# RA3003-A-1.net
KiCad netlist of a schematic drawn in Altium Designer
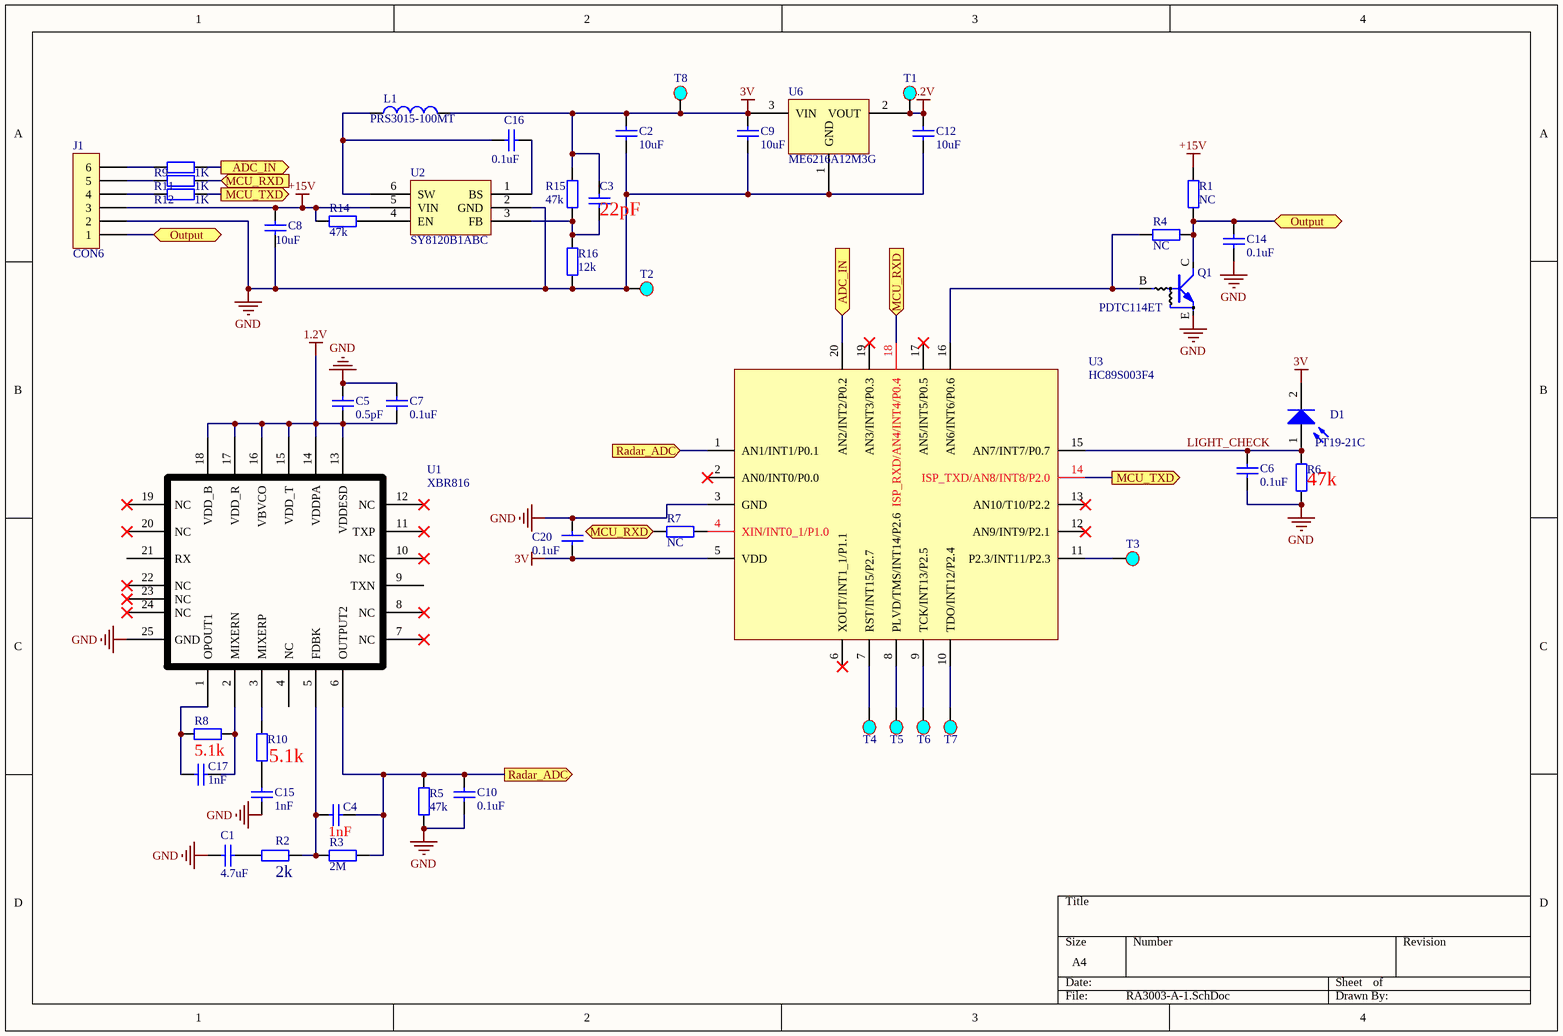
[diagram p0: RA3003-A-1.SchDoc]

(export (version "E")
  (design (tool "Eeschema 10.0.6"))
  (components
    (comp (ref "C1")
      (value "4.7uF")
      (footprint "C0402")
      (description "Capacitor")
      (fields (field (name "PUBLISHER") "Altium Limited"))
      (libsource (lib "Miscellaneous Devices") (part "Cap"))
    )
    (comp (ref "C2")
      (value "10uF")
      (footprint "C0402")
      (description "Capacitor")
      (fields (field (name "PUBLISHER") "Altium Limited"))
      (libsource (lib "Miscellaneous Devices") (part "Cap"))
    )
    (comp (ref "C3")
      (value "22pF")
      (footprint "C0402")
      (description "Capacitor")
      (fields (field (name "PUBLISHER") "Altium Limited"))
      (libsource (lib "Miscellaneous Devices") (part "Cap"))
    )
    (comp (ref "C4")
      (value "1nF")
      (footprint "C0402")
      (description "Capacitor")
      (fields (field (name "PUBLISHER") "Altium Limited"))
      (libsource (lib "Miscellaneous Devices") (part "Cap"))
    )
    (comp (ref "C5")
      (value "0.5pF")
      (footprint "C0402")
      (description "Capacitor")
      (fields (field (name "PUBLISHER") "Altium Limited"))
      (libsource (lib "Miscellaneous Devices") (part "Cap"))
    )
    (comp (ref "C6")
      (value "0.1uF")
      (footprint "C0402")
      (description "Capacitor")
      (fields (field (name "PUBLISHER") "Altium Limited"))
      (libsource (lib "Miscellaneous Devices") (part "Cap"))
    )
    (comp (ref "C7")
      (value "0.1uF")
      (footprint "C0402")
      (description "Capacitor")
      (fields (field (name "PUBLISHER") "Altium Limited"))
      (libsource (lib "Miscellaneous Devices") (part "Cap"))
    )
    (comp (ref "C8")
      (value "10uF")
      (footprint "C0603")
      (description "Capacitor")
      (fields (field (name "PUBLISHER") "Altium Limited"))
      (libsource (lib "Miscellaneous Devices") (part "Cap"))
    )
    (comp (ref "C9")
      (value "10uF")
      (footprint "C0402")
      (description "Capacitor")
      (fields (field (name "PUBLISHER") "Altium Limited"))
      (libsource (lib "Miscellaneous Devices") (part "Cap"))
    )
    (comp (ref "C10")
      (value "0.1uF")
      (footprint "C0402")
      (description "Capacitor")
      (fields (field (name "PUBLISHER") "Altium Limited"))
      (libsource (lib "Miscellaneous Devices") (part "Cap"))
    )
    (comp (ref "C12")
      (value "10uF")
      (footprint "C0402")
      (description "Capacitor")
      (fields (field (name "PUBLISHER") "Altium Limited"))
      (libsource (lib "Miscellaneous Devices") (part "Cap"))
    )
    (comp (ref "C14")
      (value "0.1uF")
      (footprint "C0402")
      (description "Capacitor")
      (fields (field (name "PUBLISHER") "Altium Limited"))
      (libsource (lib "Miscellaneous Devices") (part "Cap"))
    )
    (comp (ref "C15")
      (value "1nF")
      (footprint "C0402")
      (description "Capacitor")
      (fields (field (name "PUBLISHER") "Altium Limited"))
      (libsource (lib "Miscellaneous Devices") (part "Cap"))
    )
    (comp (ref "C16")
      (value "0.1uF")
      (footprint "C0402")
      (description "Capacitor")
      (fields (field (name "PUBLISHER") "Altium Limited"))
      (libsource (lib "Miscellaneous Devices") (part "Cap"))
    )
    (comp (ref "C17")
      (value "1nF")
      (footprint "C0402")
      (description "Capacitor")
      (fields (field (name "PUBLISHER") "Altium Limited"))
      (libsource (lib "Miscellaneous Devices") (part "Cap"))
    )
    (comp (ref "C20")
      (value "0.1uF")
      (footprint "C0402")
      (description "Capacitor")
      (fields (field (name "PUBLISHER") "Altium Limited"))
      (libsource (lib "Miscellaneous Devices") (part "Cap"))
    )
    (comp (ref "D1")
      (value "PT19-21C")
      (footprint "LED-0603")
      (description "Photosensitive Diode")
      (fields (field (name "PUBLISHER") "Altium Limited"))
      (libsource (lib "Miscellaneous Devices") (part "Photo Sen"))
    )
    (comp (ref "J1")
      (value "CON6")
      (footprint "CON 6PIN-1-2.0-DIP-P")
      (description "Connector")
      (libsource (lib "标准原理图库（特种板）") (part "CON6"))
    )
    (comp (ref "L1")
      (value "PRS3015-100MT")
      (footprint "PRS3015")
      (description "Inductor")
      (fields (field (name "PUBLISHER") "Altium Limited"))
      (libsource (lib "Miscellaneous Devices") (part "Inductor"))
    )
    (comp (ref "Q1")
      (value "PDTC114ET")
      (footprint "SOT-23(BEC)")
      (description "三极管")
      (libsource (lib "标准原理图库（特种板）") (part "PDTC114ET"))
    )
    (comp (ref "R1")
      (value "NC")
      (footprint "R0402")
      (description "Resistor")
      (fields (field (name "PUBLISHER") "Altium Limited"))
      (libsource (lib "Miscellaneous Devices") (part "Res2"))
    )
    (comp (ref "R2")
      (value "2k")
      (footprint "R0402")
      (description "Resistor")
      (fields (field (name "PUBLISHER") "Altium Limited"))
      (libsource (lib "") (part "Res2_3"))
    )
    (comp (ref "R3")
      (value "2M")
      (footprint "R0402")
      (description "Resistor")
      (fields (field (name "PUBLISHER") "Altium Limited"))
      (libsource (lib "") (part "Res2_1"))
    )
    (comp (ref "R4")
      (value "NC")
      (footprint "R0402")
      (description "Resistor")
      (fields (field (name "PUBLISHER") "Altium Limited"))
      (libsource (lib "") (part "Res2_3"))
    )
    (comp (ref "R5")
      (value "47k")
      (footprint "R0402")
      (description "Resistor")
      (fields (field (name "PUBLISHER") "Altium Limited"))
      (libsource (lib "Miscellaneous Devices") (part "Res2"))
    )
    (comp (ref "R6")
      (value "47k")
      (footprint "R0402")
      (description "Resistor")
      (fields (field (name "PUBLISHER") "Altium Limited"))
      (libsource (lib "Miscellaneous Devices") (part "Res2"))
    )
    (comp (ref "R7")
      (value "NC")
      (footprint "R0402")
      (description "Resistor")
      (fields (field (name "PUBLISHER") "Altium Limited"))
      (libsource (lib "") (part "Res2_3"))
    )
    (comp (ref "R8")
      (value "5.1k")
      (footprint "R0402")
      (description "Resistor")
      (fields (field (name "PUBLISHER") "Altium Limited"))
      (libsource (lib "") (part "Res2_1"))
    )
    (comp (ref "R9")
      (value "1K")
      (footprint "R0402")
      (description "Resistor")
      (fields (field (name "PUBLISHER") "Altium Limited"))
      (libsource (lib "") (part "Res2_1"))
    )
    (comp (ref "R10")
      (value "5.1k")
      (footprint "R0402")
      (description "Resistor")
      (fields (field (name "PUBLISHER") "Altium Limited"))
      (libsource (lib "Miscellaneous Devices") (part "Res2"))
    )
    (comp (ref "R11")
      (value "1K")
      (footprint "R0402")
      (description "Resistor")
      (fields (field (name "PUBLISHER") "Altium Limited"))
      (libsource (lib "") (part "Res2_1"))
    )
    (comp (ref "R12")
      (value "1K")
      (footprint "R0402")
      (description "Resistor")
      (fields (field (name "PUBLISHER") "Altium Limited"))
      (libsource (lib "") (part "Res2_1"))
    )
    (comp (ref "R14")
      (value "47k")
      (footprint "R0402")
      (description "Resistor")
      (fields (field (name "PUBLISHER") "Altium Limited"))
      (libsource (lib "") (part "Res2_1"))
    )
    (comp (ref "R15")
      (value "47k")
      (footprint "R0402")
      (description "Resistor")
      (fields (field (name "PUBLISHER") "Altium Limited"))
      (libsource (lib "") (part "Res2_2"))
    )
    (comp (ref "R16")
      (value "12k")
      (footprint "R0402")
      (description "Resistor")
      (fields (field (name "PUBLISHER") "Altium Limited"))
      (libsource (lib "") (part "Res2_2"))
    )
    (comp (ref "T1")
      (value "~")
      (footprint "TestPoints")
      (description "TestPoints")
      (libsource (lib "标准原理图库（特种板）") (part "TestPoints"))
    )
    (comp (ref "T2")
      (value "~")
      (footprint "TestPoints")
      (description "TestPoints")
      (libsource (lib "标准原理图库（特种板）") (part "TestPoints"))
    )
    (comp (ref "T3")
      (value "~")
      (footprint "TestPoints")
      (description "TestPoints")
      (libsource (lib "标准原理图库（特种板）") (part "TestPoints"))
    )
    (comp (ref "T4")
      (value "~")
      (footprint "TestPoints")
      (description "TestPoints")
      (libsource (lib "标准原理图库（特种板）") (part "TestPoints"))
    )
    (comp (ref "T5")
      (value "~")
      (footprint "TestPoints")
      (description "TestPoints")
      (libsource (lib "标准原理图库（特种板）") (part "TestPoints"))
    )
    (comp (ref "T6")
      (value "~")
      (footprint "TestPoints")
      (description "TestPoints")
      (libsource (lib "标准原理图库（特种板）") (part "TestPoints"))
    )
    (comp (ref "T7")
      (value "~")
      (footprint "TestPoints")
      (description "TestPoints")
      (libsource (lib "标准原理图库（特种板）") (part "TestPoints"))
    )
    (comp (ref "T8")
      (value "~")
      (footprint "TestPoints")
      (description "TestPoints")
      (libsource (lib "标准原理图库（特种板）") (part "TestPoints"))
    )
    (comp (ref "U1") (value "XBR816") (footprint "XBR816") (libsource (lib "Schlib1") (part "XBR1000_24_1")))
    (comp (ref "U2") (value "SY8120B1ABC") (footprint "SOT-23-6") (libsource (lib "Schlib1") (part "H9108")))
    (comp (ref "U3")
      (value "HC89S003F4")
      (footprint "QFN20(3*3)")
      (description "MCU")
      (libsource (lib "标准原理图库（特种板）") (part "HC89S003F4"))
    )
    (comp (ref "U6")
      (value "ME6216A12M3G")
      (footprint "SOT-23-L")
      (libsource (lib "Schlib1") (part "SSP6206"))
    )
  )
  (nets
    (net (code "1") (name "+15V") (class "Default")
      (node (ref "C8") (pin "1") (pinfunction "1_1") (pintype "passive"))
      (node (ref "J1") (pin "3") (pinfunction "3_3") (pintype "passive"))
      (node (ref "R1") (pin "1") (pinfunction "1_1") (pintype "passive"))
      (node (ref "R14") (pin "2") (pinfunction "2_2") (pintype "passive"))
      (node (ref "U2") (pin "5") (pinfunction "VIN_5") (pintype "passive"))
    )
    (net (code "2") (name "/ADC_IN") (class "Default")
      (node (ref "R9") (pin "1") (pinfunction "1_1") (pintype "passive"))
      (node (ref "U3") (pin "20") (pinfunction "AN2/INT2/P0.2_20") (pintype "passive"))
    )
    (net (code "3") (name "/LIGHT_CHECK") (class "Default")
      (node (ref "C6") (pin "1") (pinfunction "1_1") (pintype "passive"))
      (node (ref "D1") (pin "1") (pinfunction "A_1") (pintype "passive"))
      (node (ref "R6") (pin "1") (pinfunction "1_1") (pintype "passive"))
      (node (ref "U3") (pin "15") (pinfunction "AN7/INT7/P0.7_15") (pintype "passive"))
    )
    (net (code "4") (name "/MCU_RXD") (class "Default")
      (node (ref "R11") (pin "1") (pinfunction "1_1") (pintype "passive"))
      (node (ref "R7") (pin "1") (pinfunction "1_1") (pintype "passive"))
      (node (ref "U3") (pin "18") (pinfunction "ISP_RXD/AN4/INT4/P0.4_18") (pintype "passive"))
    )
    (net (code "5") (name "/MCU_TXD") (class "Default")
      (node (ref "R12") (pin "1") (pinfunction "1_1") (pintype "passive"))
      (node (ref "U3") (pin "14") (pinfunction "ISP_TXD/AN8/INT8/P2.0_14") (pintype "passive"))
    )
    (net (code "6") (name "/Output") (class "Default")
      (node (ref "C14") (pin "1") (pinfunction "1_1") (pintype "passive"))
      (node (ref "J1") (pin "1") (pinfunction "1_1") (pintype "passive"))
      (node (ref "Q1") (pin "C") (pinfunction "c_C") (pintype "passive"))
      (node (ref "R1") (pin "2") (pinfunction "2_2") (pintype "passive"))
      (node (ref "R4") (pin "2") (pinfunction "2_2") (pintype "passive"))
    )
    (net (code "7") (name "/Radar_ADC") (class "Default")
      (node (ref "C10") (pin "1") (pinfunction "1_1") (pintype "passive"))
      (node (ref "C4") (pin "1") (pinfunction "1_1") (pintype "passive"))
      (node (ref "R3") (pin "1") (pinfunction "1_1") (pintype "passive"))
      (node (ref "R5") (pin "1") (pinfunction "1_1") (pintype "passive"))
      (node (ref "U1") (pin "6") (pinfunction "OUTPUT2_6") (pintype "passive"))
      (node (ref "U3") (pin "1") (pinfunction "AN1/INT1/P0.1_1") (pintype "passive"))
    )
    (net (code "8") (name "1.2V") (class "Default")
      (node (ref "C12") (pin "1") (pinfunction "1_1") (pintype "passive"))
      (node (ref "C5") (pin "1") (pinfunction "1_1") (pintype "passive"))
      (node (ref "C7") (pin "1") (pinfunction "1_1") (pintype "passive"))
      (node (ref "T1") (pin "1") (pinfunction "1_1") (pintype "passive"))
      (node (ref "U1") (pin "13") (pinfunction "VDDESD_13") (pintype "passive"))
      (node (ref "U1") (pin "14") (pinfunction "VDDPA_14") (pintype "passive"))
      (node (ref "U1") (pin "15") (pinfunction "VDD_T_15") (pintype "passive"))
      (node (ref "U1") (pin "16") (pinfunction "VBVCO_16") (pintype "passive"))
      (node (ref "U1") (pin "17") (pinfunction "VDD_R_17") (pintype "passive"))
      (node (ref "U1") (pin "18") (pinfunction "VDD_B_18") (pintype "passive"))
      (node (ref "U6") (pin "2") (pinfunction "VOUT_2") (pintype "passive"))
    )
    (net (code "9") (name "3V") (class "Default")
      (node (ref "C2") (pin "1") (pinfunction "1_1") (pintype "passive"))
      (node (ref "C20") (pin "2") (pinfunction "2_2") (pintype "passive"))
      (node (ref "C3") (pin "2") (pinfunction "2_2") (pintype "passive"))
      (node (ref "C9") (pin "1") (pinfunction "1_1") (pintype "passive"))
      (node (ref "D1") (pin "2") (pinfunction "K_2") (pintype "passive"))
      (node (ref "L1") (pin "2") (pinfunction "2_2") (pintype "passive"))
      (node (ref "R15") (pin "2") (pinfunction "2_2") (pintype "passive"))
      (node (ref "T8") (pin "1") (pinfunction "1_1") (pintype "passive"))
      (node (ref "U3") (pin "5") (pinfunction "VDD_5") (pintype "passive"))
      (node (ref "U6") (pin "3") (pinfunction "VIN_3") (pintype "passive"))
    )
    (net (code "10") (name "GND") (class "Default")
      (node (ref "C1") (pin "2") (pinfunction "2_2") (pintype "passive"))
      (node (ref "C10") (pin "2") (pinfunction "2_2") (pintype "passive"))
      (node (ref "C12") (pin "2") (pinfunction "2_2") (pintype "passive"))
      (node (ref "C14") (pin "2") (pinfunction "2_2") (pintype "passive"))
      (node (ref "C15") (pin "1") (pinfunction "1_1") (pintype "passive"))
      (node (ref "C2") (pin "2") (pinfunction "2_2") (pintype "passive"))
      (node (ref "C20") (pin "1") (pinfunction "1_1") (pintype "passive"))
      (node (ref "C5") (pin "2") (pinfunction "2_2") (pintype "passive"))
      (node (ref "C6") (pin "2") (pinfunction "2_2") (pintype "passive"))
      (node (ref "C7") (pin "2") (pinfunction "2_2") (pintype "passive"))
      (node (ref "C8") (pin "2") (pinfunction "2_2") (pintype "passive"))
      (node (ref "C9") (pin "2") (pinfunction "2_2") (pintype "passive"))
      (node (ref "J1") (pin "2") (pinfunction "2_2") (pintype "passive"))
      (node (ref "Q1") (pin "E") (pinfunction "e_E") (pintype "passive"))
      (node (ref "R16") (pin "1") (pinfunction "1_1") (pintype "passive"))
      (node (ref "R5") (pin "2") (pinfunction "2_2") (pintype "passive"))
      (node (ref "R6") (pin "2") (pinfunction "2_2") (pintype "passive"))
      (node (ref "T2") (pin "1") (pinfunction "1_1") (pintype "passive"))
      (node (ref "U1") (pin "25") (pinfunction "GND_25") (pintype "passive"))
      (node (ref "U2") (pin "2") (pinfunction "GND_2") (pintype "passive"))
      (node (ref "U3") (pin "3") (pinfunction "GND_3") (pintype "passive"))
      (node (ref "U6") (pin "1") (pinfunction "GND_1") (pintype "passive"))
    )
    (net (code "11") (name "Net-(C1-Pad1)") (class "Default")
      (node (ref "C1") (pin "1") (pinfunction "1_1") (pintype "passive"))
      (node (ref "R2") (pin "1") (pinfunction "1_1") (pintype "passive"))
    )
    (net (code "12") (name "Net-(C15-Pad2)") (class "Default")
      (node (ref "C15") (pin "2") (pinfunction "2_2") (pintype "passive"))
      (node (ref "R10") (pin "2") (pinfunction "2_2") (pintype "passive"))
    )
    (net (code "13") (name "Net-(J1-Pad4)") (class "Default")
      (node (ref "J1") (pin "4") (pinfunction "4_4") (pintype "passive"))
      (node (ref "R12") (pin "2") (pinfunction "2_2") (pintype "passive"))
    )
    (net (code "14") (name "Net-(J1-Pad5)") (class "Default")
      (node (ref "J1") (pin "5") (pinfunction "5_5") (pintype "passive"))
      (node (ref "R11") (pin "2") (pinfunction "2_2") (pintype "passive"))
    )
    (net (code "15") (name "Net-(J1-Pad6)") (class "Default")
      (node (ref "J1") (pin "6") (pinfunction "6_6") (pintype "passive"))
      (node (ref "R9") (pin "2") (pinfunction "2_2") (pintype "passive"))
    )
    (net (code "16") (name "Net-(Q1-b)") (class "Default")
      (node (ref "Q1") (pin "B") (pinfunction "b_B") (pintype "passive"))
      (node (ref "R4") (pin "1") (pinfunction "1_1") (pintype "passive"))
      (node (ref "U3") (pin "16") (pinfunction "AN6/INT6/P0.6_16") (pintype "passive"))
    )
    (net (code "17") (name "Net-(U1-FDBK)") (class "Default")
      (node (ref "C4") (pin "2") (pinfunction "2_2") (pintype "passive"))
      (node (ref "R2") (pin "2") (pinfunction "2_2") (pintype "passive"))
      (node (ref "R3") (pin "2") (pinfunction "2_2") (pintype "passive"))
      (node (ref "U1") (pin "5") (pinfunction "FDBK_5") (pintype "passive"))
    )
    (net (code "18") (name "Net-(U1-MIXERN)") (class "Default")
      (node (ref "C17") (pin "1") (pinfunction "1_1") (pintype "passive"))
      (node (ref "R8") (pin "1") (pinfunction "1_1") (pintype "passive"))
      (node (ref "U1") (pin "2") (pinfunction "MIXERN_2") (pintype "passive"))
    )
    (net (code "19") (name "Net-(U1-MIXERP)") (class "Default")
      (node (ref "R10") (pin "1") (pinfunction "1_1") (pintype "passive"))
      (node (ref "U1") (pin "3") (pinfunction "MIXERP_3") (pintype "passive"))
    )
    (net (code "20") (name "Net-(U1-OPOUT1)") (class "Default")
      (node (ref "C17") (pin "2") (pinfunction "2_2") (pintype "passive"))
      (node (ref "R8") (pin "2") (pinfunction "2_2") (pintype "passive"))
      (node (ref "U1") (pin "1") (pinfunction "OPOUT1_1") (pintype "passive"))
    )
    (net (code "21") (name "Net-(U2-BS)") (class "Default")
      (node (ref "C16") (pin "2") (pinfunction "2_2") (pintype "passive"))
      (node (ref "U2") (pin "1") (pinfunction "BS_1") (pintype "passive"))
    )
    (net (code "22") (name "Net-(U2-EN)") (class "Default")
      (node (ref "R14") (pin "1") (pinfunction "1_1") (pintype "passive"))
      (node (ref "U2") (pin "4") (pinfunction "EN_4") (pintype "passive"))
    )
    (net (code "23") (name "Net-(U2-FB)") (class "Default")
      (node (ref "C3") (pin "1") (pinfunction "1_1") (pintype "passive"))
      (node (ref "R15") (pin "1") (pinfunction "1_1") (pintype "passive"))
      (node (ref "R16") (pin "2") (pinfunction "2_2") (pintype "passive"))
      (node (ref "U2") (pin "3") (pinfunction "FB_3") (pintype "passive"))
    )
    (net (code "24") (name "Net-(U2-SW)") (class "Default")
      (node (ref "C16") (pin "1") (pinfunction "1_1") (pintype "passive"))
      (node (ref "L1") (pin "1") (pinfunction "1_1") (pintype "passive"))
      (node (ref "U2") (pin "6") (pinfunction "SW_6") (pintype "passive"))
    )
    (net (code "25") (name "Net-(U3-P2.3{slash}INT11{slash}P2.3)") (class "Default")
      (node (ref "T3") (pin "1") (pinfunction "1_1") (pintype "passive"))
      (node (ref "U3") (pin "11") (pinfunction "P2.3/INT11/P2.3_11") (pintype "passive"))
    )
    (net (code "26") (name "Net-(U3-PLVD{slash}TMS{slash}INT14{slash}P2.6)") (class "Default")
      (node (ref "T5") (pin "1") (pinfunction "1_1") (pintype "passive"))
      (node (ref "U3") (pin "8") (pinfunction "PLVD/TMS/INT14/P2.6_8") (pintype "passive"))
    )
    (net (code "27") (name "Net-(U3-RST{slash}INT15{slash}P2.7)") (class "Default")
      (node (ref "T4") (pin "1") (pinfunction "1_1") (pintype "passive"))
      (node (ref "U3") (pin "7") (pinfunction "RST/INT15/P2.7_7") (pintype "passive"))
    )
    (net (code "28") (name "Net-(U3-TCK{slash}INT13{slash}P2.5)") (class "Default")
      (node (ref "T6") (pin "1") (pinfunction "1_1") (pintype "passive"))
      (node (ref "U3") (pin "9") (pinfunction "TCK/INT13/P2.5_9") (pintype "passive"))
    )
    (net (code "29") (name "Net-(U3-TDO{slash}INT12{slash}P2.4)") (class "Default")
      (node (ref "T7") (pin "1") (pinfunction "1_1") (pintype "passive"))
      (node (ref "U3") (pin "10") (pinfunction "TDO/INT12/P2.4_10") (pintype "passive"))
    )
    (net (code "30") (name "Net-(U3-XIN{slash}INT0_1{slash}P1.0)") (class "Default")
      (node (ref "R7") (pin "2") (pinfunction "2_2") (pintype "passive"))
      (node (ref "U3") (pin "4") (pinfunction "XIN/INT0_1/P1.0_4") (pintype "passive"))
    )
    (net (code "31") (name "unconnected-(U1-NC-Pad4)") (class "Default")
      (node (ref "U1") (pin "4") (pinfunction "NC_4") (pintype "passive"))
    )
    (net (code "32") (name "unconnected-(U1-NC-Pad7)") (class "Default")
      (node (ref "U1") (pin "7") (pinfunction "NC_7") (pintype "passive+no_connect"))
    )
    (net (code "33") (name "unconnected-(U1-NC-Pad8)") (class "Default")
      (node (ref "U1") (pin "8") (pinfunction "NC_8") (pintype "passive+no_connect"))
    )
    (net (code "34") (name "unconnected-(U1-NC-Pad10)") (class "Default")
      (node (ref "U1") (pin "10") (pinfunction "NC_10") (pintype "passive+no_connect"))
    )
    (net (code "35") (name "unconnected-(U1-NC-Pad12)") (class "Default")
      (node (ref "U1") (pin "12") (pinfunction "NC_12") (pintype "passive+no_connect"))
    )
    (net (code "36") (name "unconnected-(U1-NC-Pad19)") (class "Default")
      (node (ref "U1") (pin "19") (pinfunction "NC_19") (pintype "passive+no_connect"))
    )
    (net (code "37") (name "unconnected-(U1-NC-Pad20)") (class "Default")
      (node (ref "U1") (pin "20") (pinfunction "NC_20") (pintype "passive+no_connect"))
    )
    (net (code "38") (name "unconnected-(U1-NC-Pad22)") (class "Default")
      (node (ref "U1") (pin "22") (pinfunction "NC_22") (pintype "passive+no_connect"))
    )
    (net (code "39") (name "unconnected-(U1-NC-Pad23)") (class "Default")
      (node (ref "U1") (pin "23") (pinfunction "NC_23") (pintype "passive+no_connect"))
    )
    (net (code "40") (name "unconnected-(U1-NC-Pad24)") (class "Default")
      (node (ref "U1") (pin "24") (pinfunction "NC_24") (pintype "passive+no_connect"))
    )
    (net (code "41") (name "unconnected-(U1-RX-Pad21)") (class "Default")
      (node (ref "U1") (pin "21") (pinfunction "RX_21") (pintype "passive"))
    )
    (net (code "42") (name "unconnected-(U1-TXN-Pad9)") (class "Default")
      (node (ref "U1") (pin "9") (pinfunction "TXN_9") (pintype "passive"))
    )
    (net (code "43") (name "unconnected-(U1-TXP-Pad11)") (class "Default")
      (node (ref "U1") (pin "11") (pinfunction "TXP_11") (pintype "passive+no_connect"))
    )
    (net (code "44") (name "unconnected-(U3-AN0{slash}INT0{slash}P0.0-Pad2)") (class "Default")
      (node (ref "U3") (pin "2") (pinfunction "AN0/INT0/P0.0_2") (pintype "passive+no_connect"))
    )
    (net (code "45") (name "unconnected-(U3-AN3{slash}INT3{slash}P0.3-Pad19)") (class "Default")
      (node (ref "U3") (pin "19") (pinfunction "AN3/INT3/P0.3_19") (pintype "passive+no_connect"))
    )
    (net (code "46") (name "unconnected-(U3-AN5{slash}INT5{slash}P0.5-Pad17)") (class "Default")
      (node (ref "U3") (pin "17") (pinfunction "AN5/INT5/P0.5_17") (pintype "passive+no_connect"))
    )
    (net (code "47") (name "unconnected-(U3-AN9{slash}INT9{slash}P2.1-Pad12)") (class "Default")
      (node (ref "U3") (pin "12") (pinfunction "AN9/INT9/P2.1_12") (pintype "passive+no_connect"))
    )
    (net (code "48") (name "unconnected-(U3-AN10{slash}T10{slash}P2.2-Pad13)") (class "Default")
      (node (ref "U3") (pin "13") (pinfunction "AN10/T10/P2.2_13") (pintype "passive+no_connect"))
    )
    (net (code "49") (name "unconnected-(U3-XOUT{slash}INT1_1{slash}P1.1-Pad6)") (class "Default")
      (node (ref "U3") (pin "6") (pinfunction "XOUT/INT1_1/P1.1_6") (pintype "passive+no_connect"))
    )
  )
)
